# PIC_PROTO-BOARD-SMD.net
KiCad netlist of a schematic drawn in EAGLE
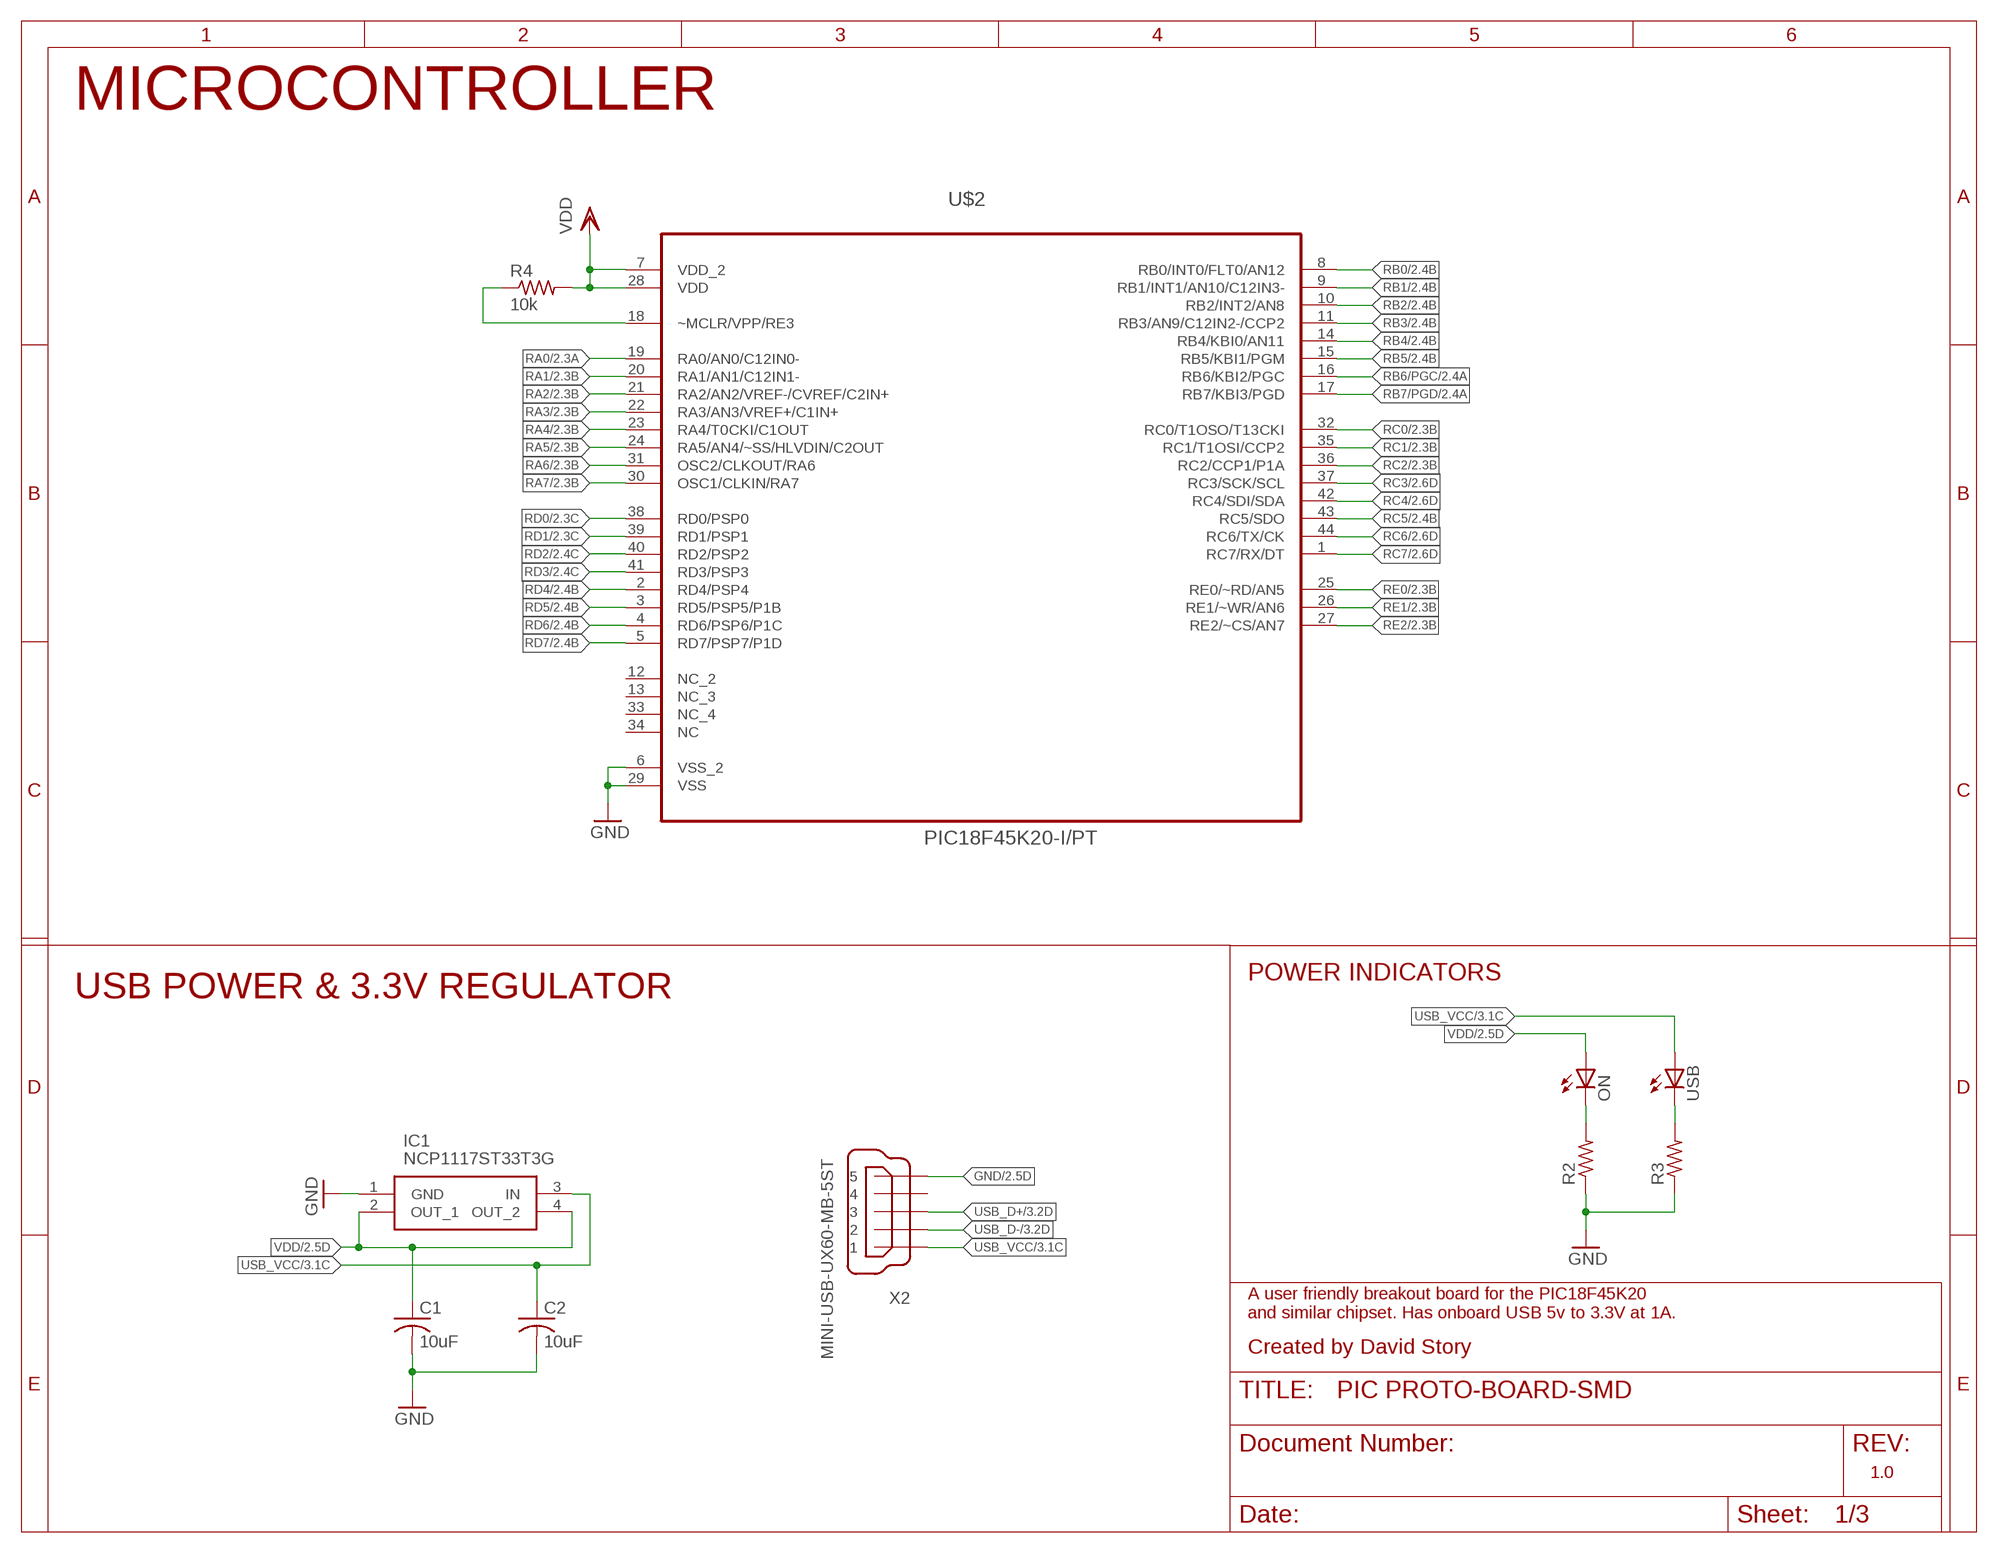
[diagram p0: schematic, sheet 1]
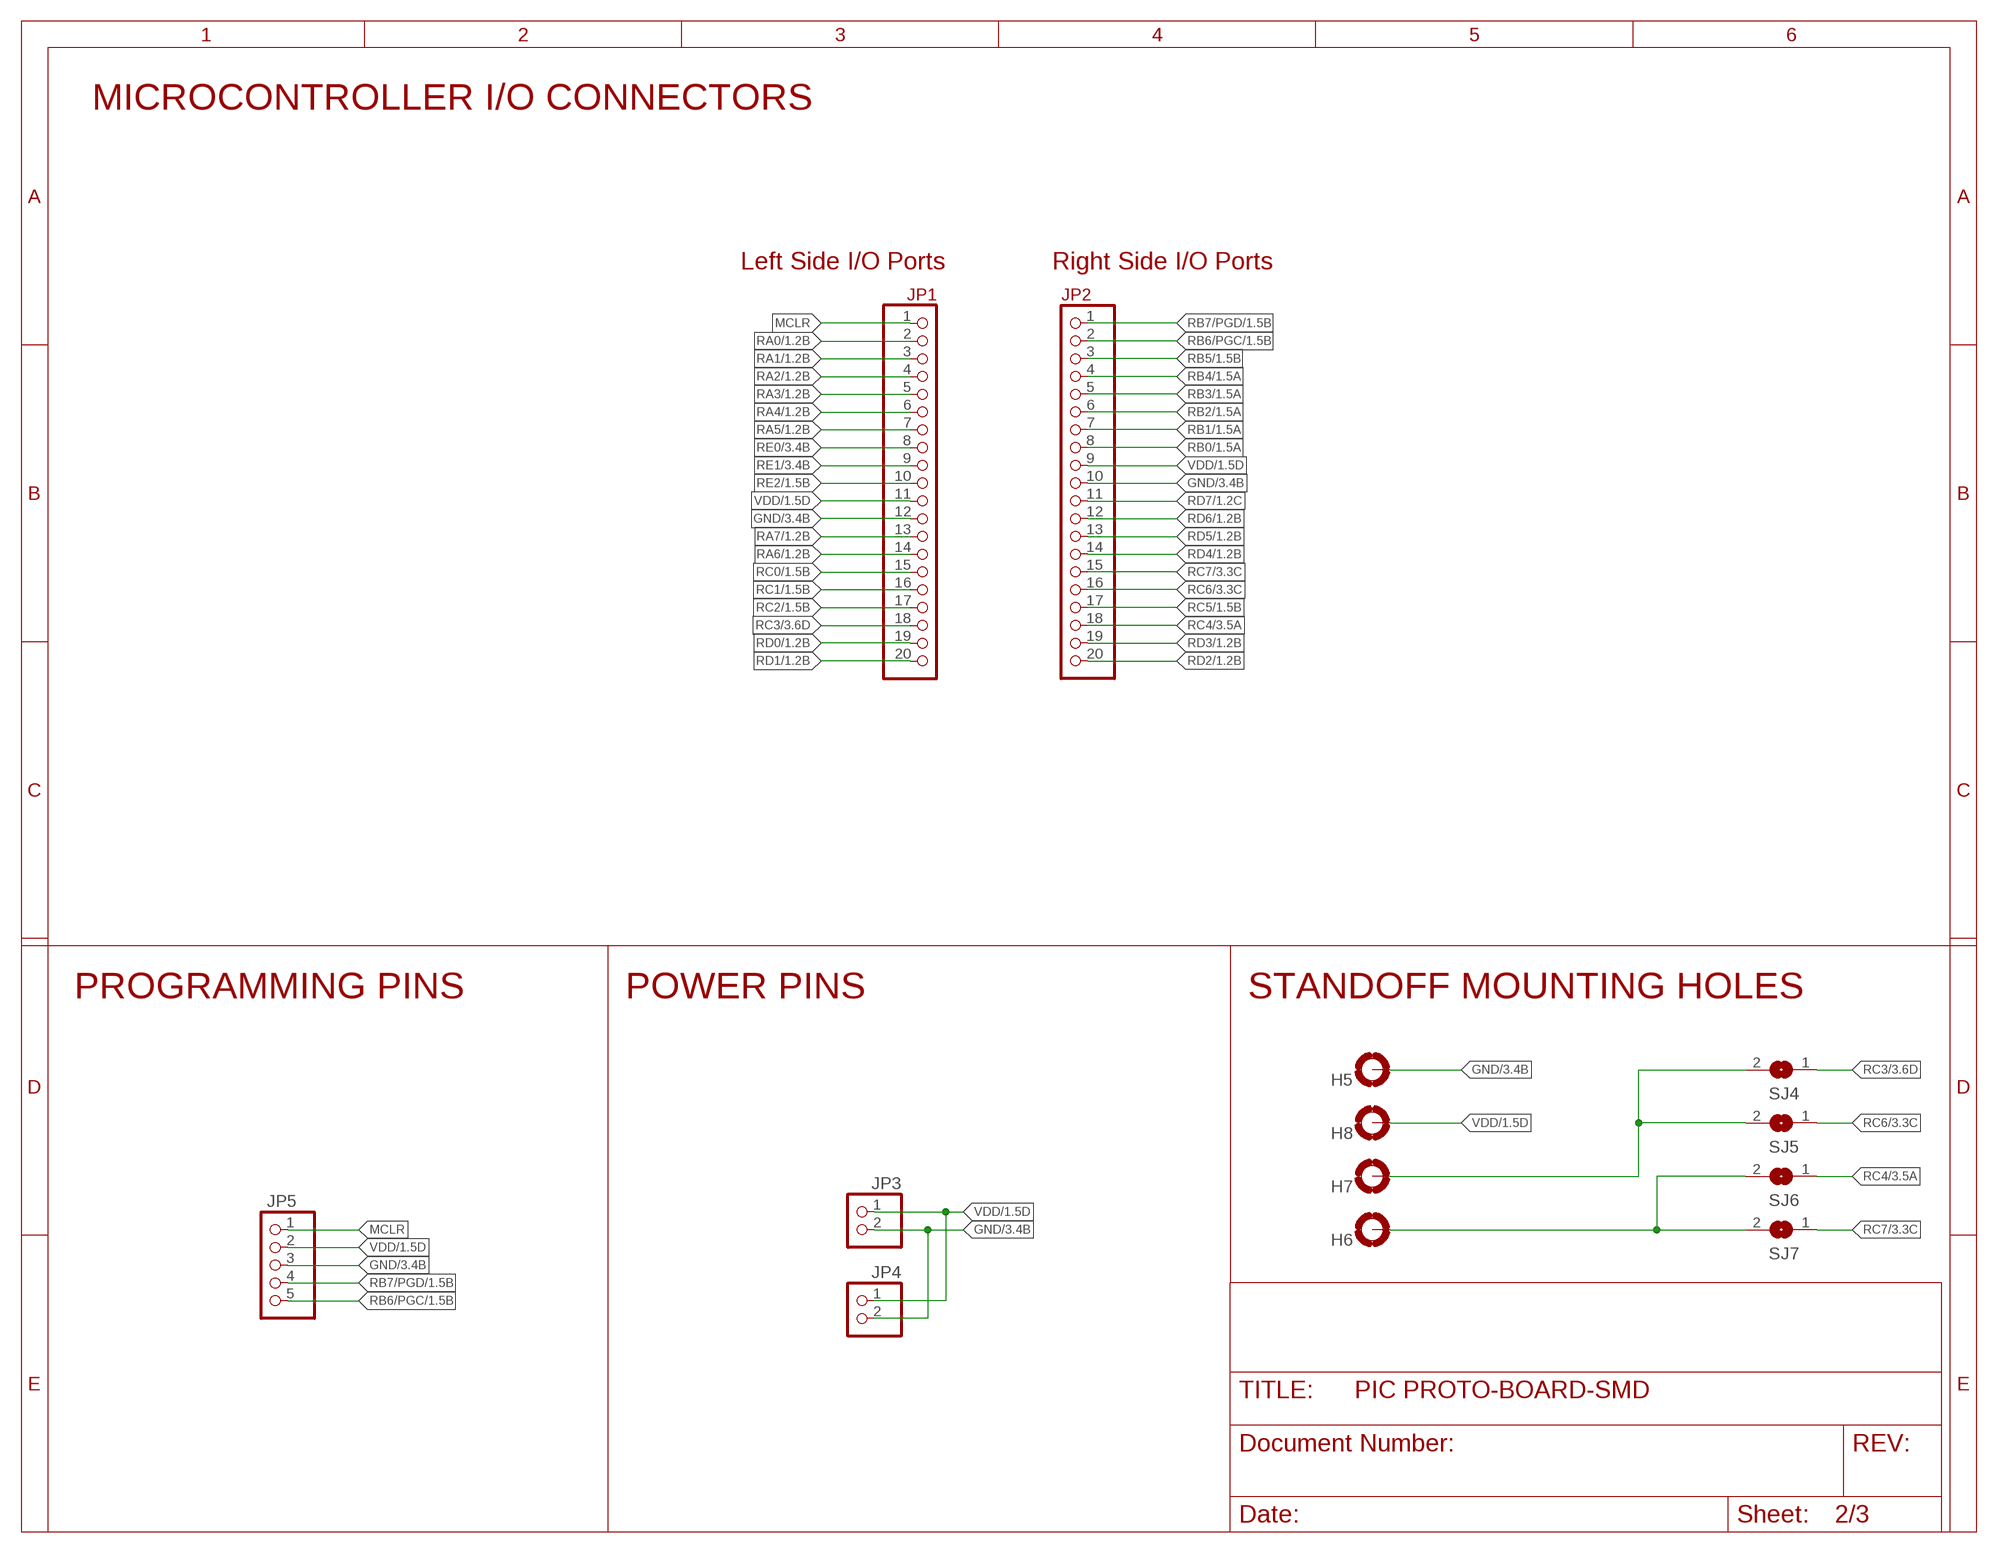
[diagram p1: schematic, sheet 2]
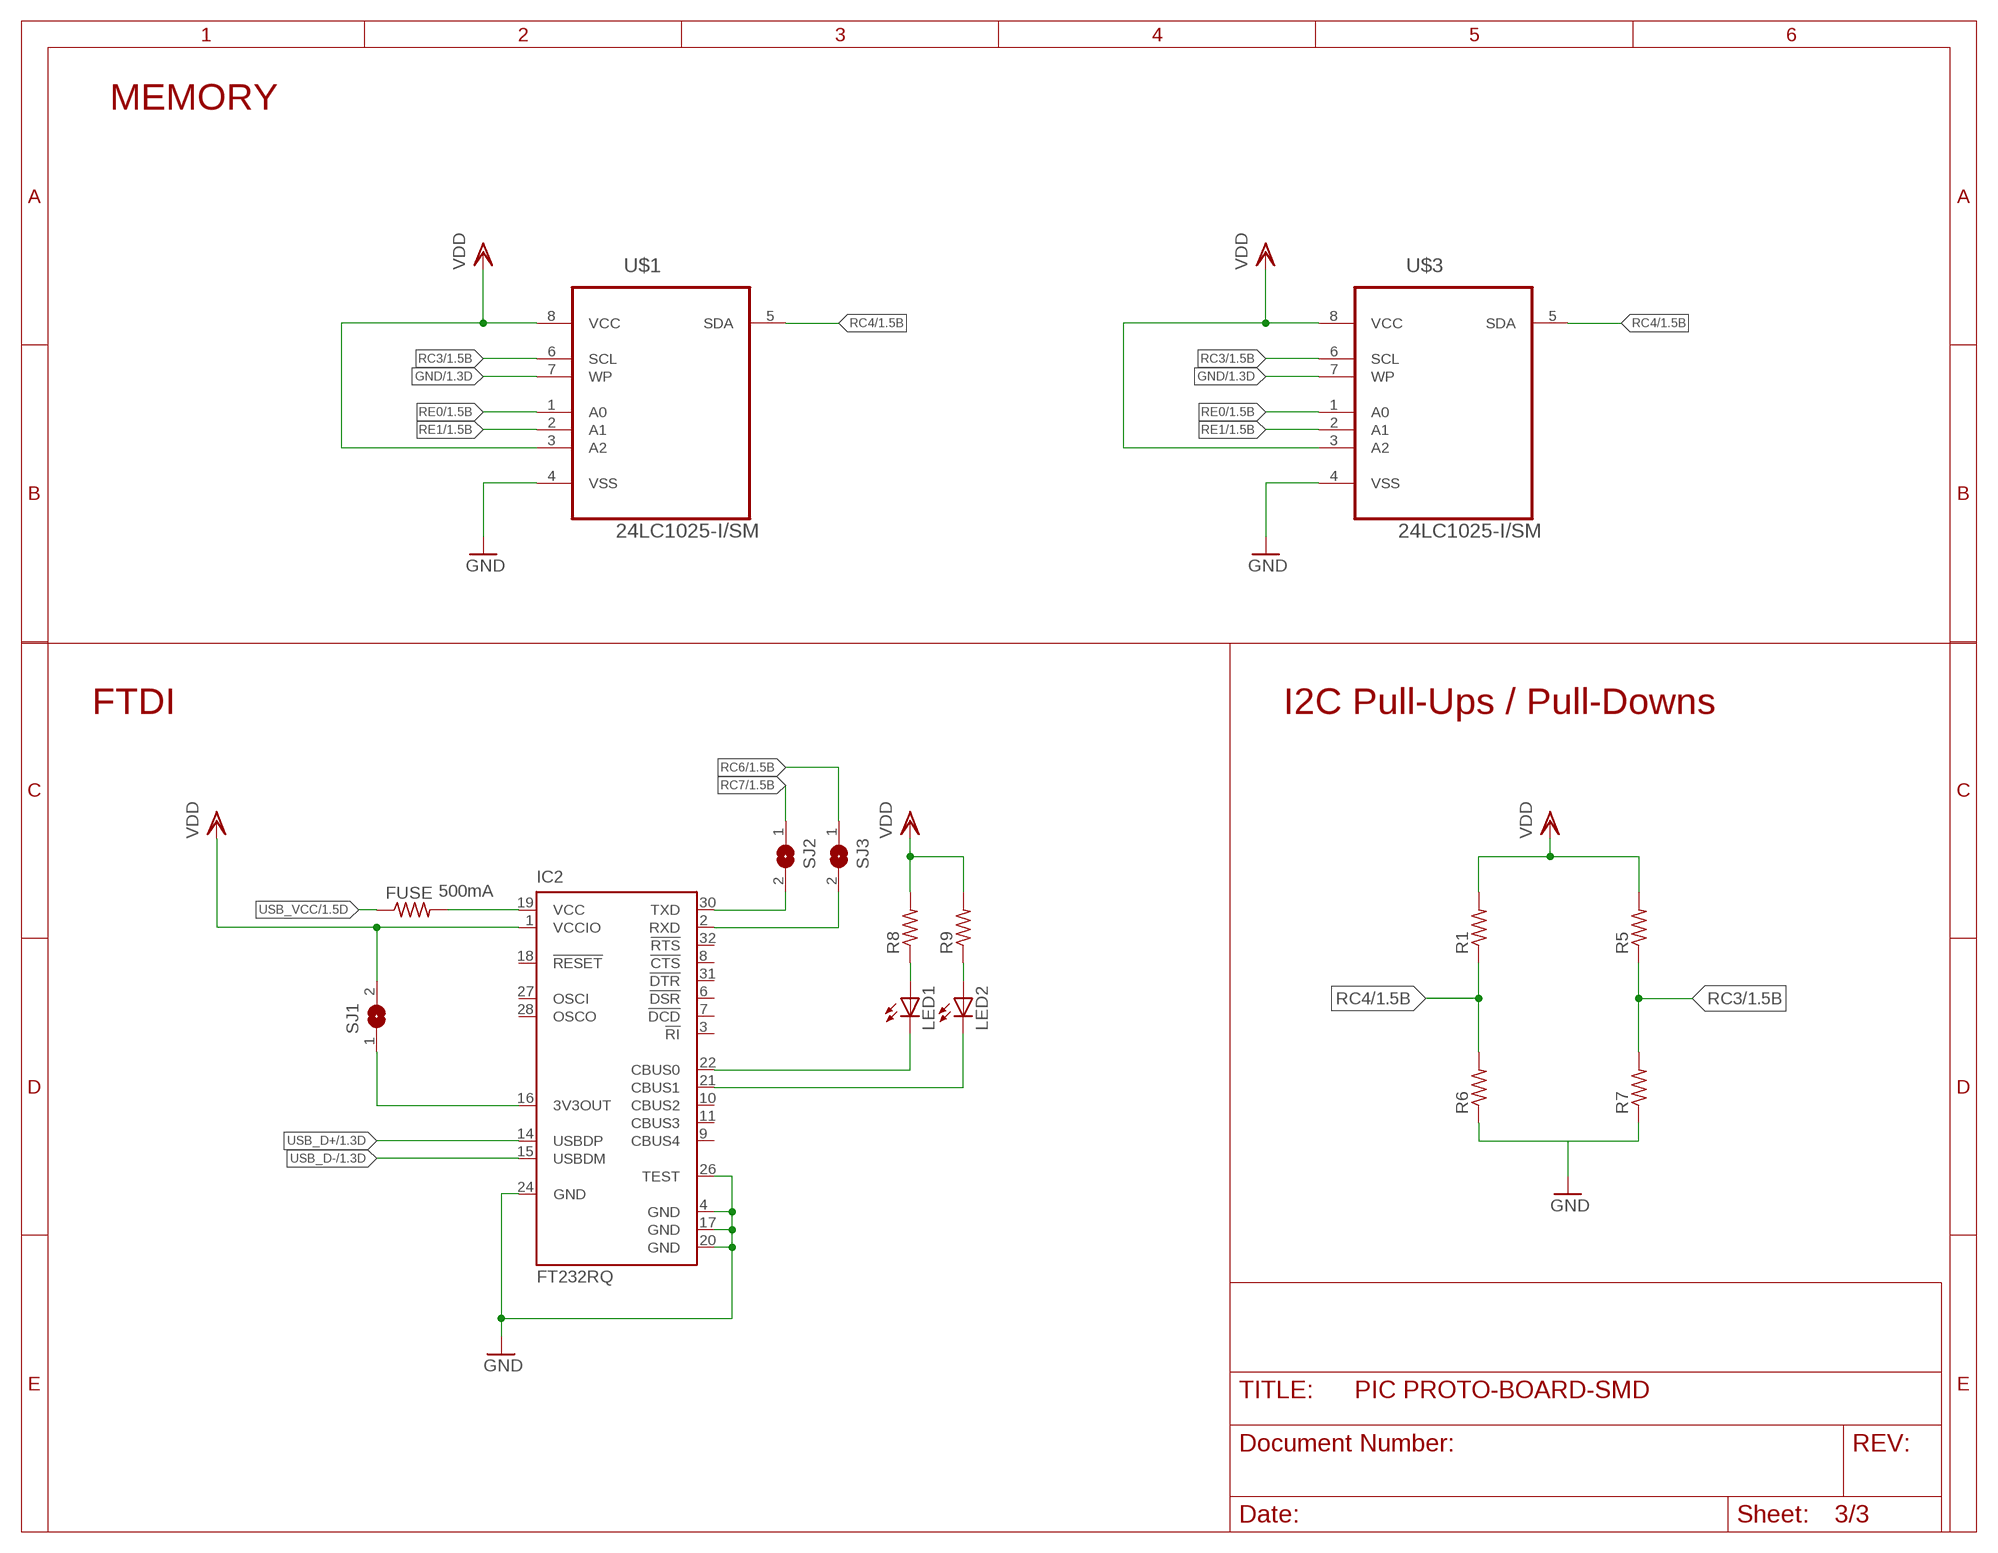
[diagram p2: schematic, sheet 3]

(export (version "E")
  (design (tool "Eeschema 10.0.6"))
  (components
    (comp (ref "C1")
      (value "10uF")
      (footprint "eagle-import:C0805")
      (libsource (lib "eagle-import") (part "C-USC0805"))
    )
    (comp (ref "C2")
      (value "10uF")
      (footprint "eagle-import:C0805")
      (libsource (lib "eagle-import") (part "C-USC0805"))
    )
    (comp (ref "IC1")
      (value "NCP1117ST33T3G")
      (footprint "eagle-import:SOT230P700X180-4N")
      (fields (field (name "MOUSER_PART_NUMBER") "863-NCP1117ST33T3G"))
      (libsource (lib "eagle-import") (part "NCP1117ST33T3G"))
    )
    (comp (ref "ON")
      (value "LEDCHIP-LED0603")
      (footprint "eagle-import:CHIP-LED0603")
      (libsource (lib "eagle-import") (part "LEDCHIP-LED0603"))
    )
    (comp (ref "R2")
      (value "R-US_R0603")
      (footprint "eagle-import:R0603")
      (libsource (lib "eagle-import") (part "R-US_R0603"))
    )
    (comp (ref "R3")
      (value "R-US_R0603")
      (footprint "eagle-import:R0603")
      (libsource (lib "eagle-import") (part "R-US_R0603"))
    )
    (comp (ref "R4")
      (value "10k")
      (footprint "eagle-import:R0805")
      (libsource (lib "eagle-import") (part "R-US_R0805"))
    )
    (comp (ref "U$2")
      (value "PIC18F45K20-I/PT")
      (footprint "eagle-import:QFP80P1200X1200X120-44N")
      (libsource (lib "eagle-import") (part "PIC18F45K20-I/PT"))
    )
    (comp (ref "USB")
      (value "LEDCHIP-LED0603")
      (footprint "eagle-import:CHIP-LED0603")
      (libsource (lib "eagle-import") (part "LEDCHIP-LED0603"))
    )
    (comp (ref "X2")
      (value "MINI-USB-UX60-MB-5ST")
      (footprint "eagle-import:UX60-MB-5ST")
      (libsource (lib "eagle-import") (part "MINI-USB-UX60-MB-5ST"))
    )
    (comp (ref "H5")
      (value "MOUNT-PAD-ROUND3.3")
      (footprint "eagle-import:3,3-PAD")
      (libsource (lib "eagle-import") (part "MOUNT-PAD-ROUND3.3"))
    )
    (comp (ref "H6")
      (value "MOUNT-PAD-ROUND3.3")
      (footprint "eagle-import:3,3-PAD")
      (libsource (lib "eagle-import") (part "MOUNT-PAD-ROUND3.3"))
    )
    (comp (ref "H7")
      (value "MOUNT-PAD-ROUND3.3")
      (footprint "eagle-import:3,3-PAD")
      (libsource (lib "eagle-import") (part "MOUNT-PAD-ROUND3.3"))
    )
    (comp (ref "H8")
      (value "MOUNT-PAD-ROUND3.3")
      (footprint "eagle-import:3,3-PAD")
      (libsource (lib "eagle-import") (part "MOUNT-PAD-ROUND3.3"))
    )
    (comp (ref "JP1")
      (value "PINHD-1X20")
      (footprint "eagle-import:1X20")
      (libsource (lib "eagle-import") (part "PINHD-1X20"))
    )
    (comp (ref "JP2")
      (value "PINHD-1X20")
      (footprint "eagle-import:1X20")
      (libsource (lib "eagle-import") (part "PINHD-1X20"))
    )
    (comp (ref "JP3")
      (value "PINHD-1X2")
      (footprint "eagle-import:1X02")
      (libsource (lib "eagle-import") (part "PINHD-1X2"))
    )
    (comp (ref "JP4")
      (value "PINHD-1X2")
      (footprint "eagle-import:1X02")
      (libsource (lib "eagle-import") (part "PINHD-1X2"))
    )
    (comp (ref "JP5")
      (value "PINHD-1X5")
      (footprint "eagle-import:1X05")
      (libsource (lib "eagle-import") (part "PINHD-1X5"))
    )
    (comp (ref "SJ4") (value "SJ") (footprint "eagle-import:SJ") (libsource (lib "eagle-import") (part "SJ")))
    (comp (ref "SJ5") (value "SJ") (footprint "eagle-import:SJ") (libsource (lib "eagle-import") (part "SJ")))
    (comp (ref "SJ6") (value "SJ") (footprint "eagle-import:SJ") (libsource (lib "eagle-import") (part "SJ")))
    (comp (ref "SJ7") (value "SJ") (footprint "eagle-import:SJ") (libsource (lib "eagle-import") (part "SJ")))
    (comp (ref "FUSE")
      (value "500mA")
      (footprint "eagle-import:M0805")
      (libsource (lib "eagle-import") (part "R-US_M0805"))
    )
    (comp (ref "IC2")
      (value "FT232RQ")
      (footprint "eagle-import:QFN32")
      (libsource (lib "eagle-import") (part "FT232RQ"))
    )
    (comp (ref "LED1")
      (value "LEDSML0603")
      (footprint "eagle-import:SML0603")
      (libsource (lib "eagle-import") (part "LEDSML0603"))
    )
    (comp (ref "LED2")
      (value "LEDSML0603")
      (footprint "eagle-import:SML0603")
      (libsource (lib "eagle-import") (part "LEDSML0603"))
    )
    (comp (ref "R1")
      (value "R-US_R0805")
      (footprint "eagle-import:R0805")
      (libsource (lib "eagle-import") (part "R-US_R0805"))
    )
    (comp (ref "R5")
      (value "R-US_R0805")
      (footprint "eagle-import:R0805")
      (libsource (lib "eagle-import") (part "R-US_R0805"))
    )
    (comp (ref "R6")
      (value "R-US_R0805")
      (footprint "eagle-import:R0805")
      (libsource (lib "eagle-import") (part "R-US_R0805"))
    )
    (comp (ref "R7")
      (value "R-US_R0805")
      (footprint "eagle-import:R0805")
      (libsource (lib "eagle-import") (part "R-US_R0805"))
    )
    (comp (ref "R8")
      (value "R-US_R0805")
      (footprint "eagle-import:R0805")
      (libsource (lib "eagle-import") (part "R-US_R0805"))
    )
    (comp (ref "R9")
      (value "R-US_R0805")
      (footprint "eagle-import:R0805")
      (libsource (lib "eagle-import") (part "R-US_R0805"))
    )
    (comp (ref "SJ1") (value "SJ") (footprint "eagle-import:SJ") (libsource (lib "eagle-import") (part "SJ")))
    (comp (ref "SJ2") (value "SJ") (footprint "eagle-import:SJ") (libsource (lib "eagle-import") (part "SJ")))
    (comp (ref "SJ3") (value "SJ") (footprint "eagle-import:SJ") (libsource (lib "eagle-import") (part "SJ")))
    (comp (ref "U$1")
      (value "24LC1025-I/SM")
      (footprint "eagle-import:SOIC127P794X203-8N")
      (libsource (lib "eagle-import") (part "24LC1025-I/SM"))
    )
    (comp (ref "U$3")
      (value "24LC1025-I/SM")
      (footprint "eagle-import:SOIC127P794X203-8N")
      (libsource (lib "eagle-import") (part "24LC1025-I/SM"))
    )
  )
  (nets
    (net (code "1") (name "GND") (class "Default")
      (node (ref "C1") (pin "2") (pinfunction "2_2") (pintype "passive"))
      (node (ref "C2") (pin "2") (pinfunction "2_2") (pintype "passive"))
      (node (ref "H5") (pin "B3,3") (pinfunction "MOUNT_B3,3") (pintype "passive"))
      (node (ref "IC1") (pin "1") (pinfunction "GND_1") (pintype "power_in"))
      (node (ref "IC2") (pin "17") (pinfunction "GND_17") (pintype "power_in"))
      (node (ref "IC2") (pin "20") (pinfunction "GND_20") (pintype "power_in"))
      (node (ref "IC2") (pin "24") (pinfunction "GND_24") (pintype "power_in"))
      (node (ref "IC2") (pin "26") (pinfunction "TEST_26") (pintype "input"))
      (node (ref "IC2") (pin "4") (pinfunction "GND_4") (pintype "power_in"))
      (node (ref "JP1") (pin "12") (pinfunction "12_12") (pintype "passive"))
      (node (ref "JP2") (pin "10") (pinfunction "10_10") (pintype "passive"))
      (node (ref "JP3") (pin "2") (pinfunction "2_2") (pintype "passive"))
      (node (ref "JP4") (pin "2") (pinfunction "2_2") (pintype "passive"))
      (node (ref "JP5") (pin "3") (pinfunction "3_3") (pintype "passive"))
      (node (ref "R2") (pin "1") (pinfunction "1_1") (pintype "passive"))
      (node (ref "R3") (pin "1") (pinfunction "1_1") (pintype "passive"))
      (node (ref "R6") (pin "1") (pinfunction "1_1") (pintype "passive"))
      (node (ref "R7") (pin "1") (pinfunction "1_1") (pintype "passive"))
      (node (ref "U$1") (pin "4") (pinfunction "VSS_4") (pintype "passive"))
      (node (ref "U$1") (pin "7") (pinfunction "WP_7") (pintype "input"))
      (node (ref "U$2") (pin "29") (pinfunction "VSS_29") (pintype "power_in"))
      (node (ref "U$2") (pin "6") (pinfunction "VSS_2_6") (pintype "power_in"))
      (node (ref "U$3") (pin "4") (pinfunction "VSS_4") (pintype "passive"))
      (node (ref "U$3") (pin "7") (pinfunction "WP_7") (pintype "input"))
      (node (ref "X2") (pin "5") (pinfunction "5_5") (pintype "input"))
    )
    (net (code "2") (name "MCLR") (class "Default")
      (node (ref "JP1") (pin "1") (pinfunction "1_1") (pintype "passive"))
      (node (ref "JP5") (pin "1") (pinfunction "1_1") (pintype "passive"))
      (node (ref "R4") (pin "1") (pinfunction "1_1") (pintype "passive"))
      (node (ref "U$2") (pin "18") (pinfunction "~{MCLR/VPP/RE3}_18") (pintype "input"))
    )
    (net (code "3") (name "Net-(H6-MOUNT)") (class "Default")
      (node (ref "H6") (pin "B3,3") (pinfunction "MOUNT_B3,3") (pintype "passive"))
      (node (ref "SJ6") (pin "2") (pinfunction "2_2") (pintype "passive"))
      (node (ref "SJ7") (pin "2") (pinfunction "2_2") (pintype "passive"))
    )
    (net (code "4") (name "Net-(H7-MOUNT)") (class "Default")
      (node (ref "H7") (pin "B3,3") (pinfunction "MOUNT_B3,3") (pintype "passive"))
      (node (ref "SJ4") (pin "2") (pinfunction "2_2") (pintype "passive"))
      (node (ref "SJ5") (pin "2") (pinfunction "2_2") (pintype "passive"))
    )
    (net (code "5") (name "Net-(IC2-3V3OUT)") (class "Default")
      (node (ref "IC2") (pin "16") (pinfunction "3V3OUT_16") (pintype "output"))
      (node (ref "SJ1") (pin "1") (pinfunction "1_1") (pintype "passive"))
    )
    (net (code "6") (name "Net-(IC2-CBUS0)") (class "Default")
      (node (ref "IC2") (pin "22") (pinfunction "CBUS0_22") (pintype "bidirectional"))
      (node (ref "LED1") (pin "C") (pinfunction "C_C") (pintype "passive"))
    )
    (net (code "7") (name "Net-(IC2-CBUS1)") (class "Default")
      (node (ref "IC2") (pin "21") (pinfunction "CBUS1_21") (pintype "bidirectional"))
      (node (ref "LED2") (pin "C") (pinfunction "C_C") (pintype "passive"))
    )
    (net (code "8") (name "Net-(IC2-RXD)") (class "Default")
      (node (ref "IC2") (pin "2") (pinfunction "RXD_2") (pintype "input"))
      (node (ref "SJ3") (pin "2") (pinfunction "2_2") (pintype "passive"))
    )
    (net (code "9") (name "Net-(IC2-TXD)") (class "Default")
      (node (ref "IC2") (pin "30") (pinfunction "TXD_30") (pintype "output"))
      (node (ref "SJ2") (pin "2") (pinfunction "2_2") (pintype "passive"))
    )
    (net (code "10") (name "Net-(IC2-VCC)") (class "Default")
      (node (ref "FUSE") (pin "2") (pinfunction "2_2") (pintype "passive"))
      (node (ref "IC2") (pin "19") (pinfunction "VCC_19") (pintype "power_in"))
    )
    (net (code "11") (name "Net-(LED1-PadA)") (class "Default")
      (node (ref "LED1") (pin "A") (pinfunction "A_A") (pintype "passive"))
      (node (ref "R8") (pin "1") (pinfunction "1_1") (pintype "passive"))
    )
    (net (code "12") (name "Net-(LED2-PadA)") (class "Default")
      (node (ref "LED2") (pin "A") (pinfunction "A_A") (pintype "passive"))
      (node (ref "R9") (pin "1") (pinfunction "1_1") (pintype "passive"))
    )
    (net (code "13") (name "Net-(ON-PadC)") (class "Default")
      (node (ref "ON") (pin "C") (pinfunction "C_C") (pintype "passive"))
      (node (ref "R2") (pin "2") (pinfunction "2_2") (pintype "passive"))
    )
    (net (code "14") (name "Net-(R3-Pad2)") (class "Default")
      (node (ref "R3") (pin "2") (pinfunction "2_2") (pintype "passive"))
      (node (ref "USB") (pin "C") (pinfunction "C_C") (pintype "passive"))
    )
    (net (code "15") (name "RA0") (class "Default")
      (node (ref "JP1") (pin "2") (pinfunction "2_2") (pintype "passive"))
      (node (ref "U$2") (pin "19") (pinfunction "RA0/AN0/C12IN0-_19") (pintype "bidirectional"))
    )
    (net (code "16") (name "RA1") (class "Default")
      (node (ref "JP1") (pin "3") (pinfunction "3_3") (pintype "passive"))
      (node (ref "U$2") (pin "20") (pinfunction "RA1/AN1/C12IN1-_20") (pintype "bidirectional"))
    )
    (net (code "17") (name "RA2") (class "Default")
      (node (ref "JP1") (pin "4") (pinfunction "4_4") (pintype "passive"))
      (node (ref "U$2") (pin "21") (pinfunction "RA2/AN2/VREF-/CVREF/C2IN+_21") (pintype "bidirectional"))
    )
    (net (code "18") (name "RA3") (class "Default")
      (node (ref "JP1") (pin "5") (pinfunction "5_5") (pintype "passive"))
      (node (ref "U$2") (pin "22") (pinfunction "RA3/AN3/VREF+/C1IN+_22") (pintype "bidirectional"))
    )
    (net (code "19") (name "RA4") (class "Default")
      (node (ref "JP1") (pin "6") (pinfunction "6_6") (pintype "passive"))
      (node (ref "U$2") (pin "23") (pinfunction "RA4/T0CKI/C1OUT_23") (pintype "bidirectional"))
    )
    (net (code "20") (name "RA5") (class "Default")
      (node (ref "JP1") (pin "7") (pinfunction "7_7") (pintype "passive"))
      (node (ref "U$2") (pin "24") (pinfunction "RA5/AN4/~{SS/HLVDIN/C2OUT}_24") (pintype "bidirectional"))
    )
    (net (code "21") (name "RA6") (class "Default")
      (node (ref "JP1") (pin "14") (pinfunction "14_14") (pintype "passive"))
      (node (ref "U$2") (pin "31") (pinfunction "OSC2/CLKOUT/RA6_31") (pintype "bidirectional"))
    )
    (net (code "22") (name "RA7") (class "Default")
      (node (ref "JP1") (pin "13") (pinfunction "13_13") (pintype "passive"))
      (node (ref "U$2") (pin "30") (pinfunction "OSC1/CLKIN/RA7_30") (pintype "bidirectional"))
    )
    (net (code "23") (name "RB0") (class "Default")
      (node (ref "JP2") (pin "8") (pinfunction "8_8") (pintype "passive"))
      (node (ref "U$2") (pin "8") (pinfunction "RB0/INT0/FLT0/AN12_8") (pintype "bidirectional"))
    )
    (net (code "24") (name "RB1") (class "Default")
      (node (ref "JP2") (pin "7") (pinfunction "7_7") (pintype "passive"))
      (node (ref "U$2") (pin "9") (pinfunction "RB1/INT1/AN10/C12IN3-_9") (pintype "bidirectional"))
    )
    (net (code "25") (name "RB2") (class "Default")
      (node (ref "JP2") (pin "6") (pinfunction "6_6") (pintype "passive"))
      (node (ref "U$2") (pin "10") (pinfunction "RB2/INT2/AN8_10") (pintype "bidirectional"))
    )
    (net (code "26") (name "RB3") (class "Default")
      (node (ref "JP2") (pin "5") (pinfunction "5_5") (pintype "passive"))
      (node (ref "U$2") (pin "11") (pinfunction "RB3/AN9/C12IN2-/CCP2_11") (pintype "bidirectional"))
    )
    (net (code "27") (name "RB4") (class "Default")
      (node (ref "JP2") (pin "4") (pinfunction "4_4") (pintype "passive"))
      (node (ref "U$2") (pin "14") (pinfunction "RB4/KBI0/AN11_14") (pintype "bidirectional"))
    )
    (net (code "28") (name "RB5") (class "Default")
      (node (ref "JP2") (pin "3") (pinfunction "3_3") (pintype "passive"))
      (node (ref "U$2") (pin "15") (pinfunction "RB5/KBI1/PGM_15") (pintype "bidirectional"))
    )
    (net (code "29") (name "RB6{slash}PGC") (class "Default")
      (node (ref "JP2") (pin "2") (pinfunction "2_2") (pintype "passive"))
      (node (ref "JP5") (pin "5") (pinfunction "5_5") (pintype "passive"))
      (node (ref "U$2") (pin "16") (pinfunction "RB6/KBI2/PGC_16") (pintype "bidirectional"))
    )
    (net (code "30") (name "RB7{slash}PGD") (class "Default")
      (node (ref "JP2") (pin "1") (pinfunction "1_1") (pintype "passive"))
      (node (ref "JP5") (pin "4") (pinfunction "4_4") (pintype "passive"))
      (node (ref "U$2") (pin "17") (pinfunction "RB7/KBI3/PGD_17") (pintype "bidirectional"))
    )
    (net (code "31") (name "RC0") (class "Default")
      (node (ref "JP1") (pin "15") (pinfunction "15_15") (pintype "passive"))
      (node (ref "U$2") (pin "32") (pinfunction "RC0/T1OSO/T13CKI_32") (pintype "bidirectional"))
    )
    (net (code "32") (name "RC1") (class "Default")
      (node (ref "JP1") (pin "16") (pinfunction "16_16") (pintype "passive"))
      (node (ref "U$2") (pin "35") (pinfunction "RC1/T1OSI/CCP2_35") (pintype "bidirectional"))
    )
    (net (code "33") (name "RC2") (class "Default")
      (node (ref "JP1") (pin "17") (pinfunction "17_17") (pintype "passive"))
      (node (ref "U$2") (pin "36") (pinfunction "RC2/CCP1/P1A_36") (pintype "bidirectional"))
    )
    (net (code "34") (name "RC3") (class "Default")
      (node (ref "JP1") (pin "18") (pinfunction "18_18") (pintype "passive"))
      (node (ref "R5") (pin "1") (pinfunction "1_1") (pintype "passive"))
      (node (ref "R7") (pin "2") (pinfunction "2_2") (pintype "passive"))
      (node (ref "SJ4") (pin "1") (pinfunction "1_1") (pintype "passive"))
      (node (ref "U$1") (pin "6") (pinfunction "SCL_6") (pintype "input"))
      (node (ref "U$2") (pin "37") (pinfunction "RC3/SCK/SCL_37") (pintype "bidirectional"))
      (node (ref "U$3") (pin "6") (pinfunction "SCL_6") (pintype "input"))
    )
    (net (code "35") (name "RC4") (class "Default")
      (node (ref "JP2") (pin "18") (pinfunction "18_18") (pintype "passive"))
      (node (ref "R1") (pin "1") (pinfunction "1_1") (pintype "passive"))
      (node (ref "R6") (pin "2") (pinfunction "2_2") (pintype "passive"))
      (node (ref "SJ6") (pin "1") (pinfunction "1_1") (pintype "passive"))
      (node (ref "U$1") (pin "5") (pinfunction "SDA_5") (pintype "bidirectional"))
      (node (ref "U$2") (pin "42") (pinfunction "RC4/SDI/SDA_42") (pintype "bidirectional"))
      (node (ref "U$3") (pin "5") (pinfunction "SDA_5") (pintype "bidirectional"))
    )
    (net (code "36") (name "RC5") (class "Default")
      (node (ref "JP2") (pin "17") (pinfunction "17_17") (pintype "passive"))
      (node (ref "U$2") (pin "43") (pinfunction "RC5/SDO_43") (pintype "bidirectional"))
    )
    (net (code "37") (name "RC6") (class "Default")
      (node (ref "JP2") (pin "16") (pinfunction "16_16") (pintype "passive"))
      (node (ref "SJ3") (pin "1") (pinfunction "1_1") (pintype "passive"))
      (node (ref "SJ5") (pin "1") (pinfunction "1_1") (pintype "passive"))
      (node (ref "U$2") (pin "44") (pinfunction "RC6/TX/CK_44") (pintype "bidirectional"))
    )
    (net (code "38") (name "RC7") (class "Default")
      (node (ref "JP2") (pin "15") (pinfunction "15_15") (pintype "passive"))
      (node (ref "SJ2") (pin "1") (pinfunction "1_1") (pintype "passive"))
      (node (ref "SJ7") (pin "1") (pinfunction "1_1") (pintype "passive"))
      (node (ref "U$2") (pin "1") (pinfunction "RC7/RX/DT_1") (pintype "bidirectional"))
    )
    (net (code "39") (name "RD0") (class "Default")
      (node (ref "JP1") (pin "19") (pinfunction "19_19") (pintype "passive"))
      (node (ref "U$2") (pin "38") (pinfunction "RD0/PSP0_38") (pintype "bidirectional"))
    )
    (net (code "40") (name "RD1") (class "Default")
      (node (ref "JP1") (pin "20") (pinfunction "20_20") (pintype "passive"))
      (node (ref "U$2") (pin "39") (pinfunction "RD1/PSP1_39") (pintype "bidirectional"))
    )
    (net (code "41") (name "RD2") (class "Default")
      (node (ref "JP2") (pin "20") (pinfunction "20_20") (pintype "passive"))
      (node (ref "U$2") (pin "40") (pinfunction "RD2/PSP2_40") (pintype "bidirectional"))
    )
    (net (code "42") (name "RD3") (class "Default")
      (node (ref "JP2") (pin "19") (pinfunction "19_19") (pintype "passive"))
      (node (ref "U$2") (pin "41") (pinfunction "RD3/PSP3_41") (pintype "bidirectional"))
    )
    (net (code "43") (name "RD4") (class "Default")
      (node (ref "JP2") (pin "14") (pinfunction "14_14") (pintype "passive"))
      (node (ref "U$2") (pin "2") (pinfunction "RD4/PSP4_2") (pintype "bidirectional"))
    )
    (net (code "44") (name "RD5") (class "Default")
      (node (ref "JP2") (pin "13") (pinfunction "13_13") (pintype "passive"))
      (node (ref "U$2") (pin "3") (pinfunction "RD5/PSP5/P1B_3") (pintype "bidirectional"))
    )
    (net (code "45") (name "RD6") (class "Default")
      (node (ref "JP2") (pin "12") (pinfunction "12_12") (pintype "passive"))
      (node (ref "U$2") (pin "4") (pinfunction "RD6/PSP6/P1C_4") (pintype "bidirectional"))
    )
    (net (code "46") (name "RD7") (class "Default")
      (node (ref "JP2") (pin "11") (pinfunction "11_11") (pintype "passive"))
      (node (ref "U$2") (pin "5") (pinfunction "RD7/PSP7/P1D_5") (pintype "bidirectional"))
    )
    (net (code "47") (name "RE0") (class "Default")
      (node (ref "JP1") (pin "8") (pinfunction "8_8") (pintype "passive"))
      (node (ref "U$1") (pin "1") (pinfunction "A0_1") (pintype "input"))
      (node (ref "U$2") (pin "25") (pinfunction "RE0/~{RD/AN5}_25") (pintype "bidirectional"))
      (node (ref "U$3") (pin "1") (pinfunction "A0_1") (pintype "input"))
    )
    (net (code "48") (name "RE1") (class "Default")
      (node (ref "JP1") (pin "9") (pinfunction "9_9") (pintype "passive"))
      (node (ref "U$1") (pin "2") (pinfunction "A1_2") (pintype "input"))
      (node (ref "U$2") (pin "26") (pinfunction "RE1/~{WR/AN6}_26") (pintype "bidirectional"))
      (node (ref "U$3") (pin "2") (pinfunction "A1_2") (pintype "input"))
    )
    (net (code "49") (name "RE2") (class "Default")
      (node (ref "JP1") (pin "10") (pinfunction "10_10") (pintype "passive"))
      (node (ref "U$2") (pin "27") (pinfunction "RE2/~{CS/AN7}_27") (pintype "bidirectional"))
    )
    (net (code "50") (name "USB_D+") (class "Default")
      (node (ref "IC2") (pin "14") (pinfunction "USBDP_14") (pintype "bidirectional"))
      (node (ref "X2") (pin "3") (pinfunction "3_3") (pintype "input"))
    )
    (net (code "51") (name "USB_D-") (class "Default")
      (node (ref "IC2") (pin "15") (pinfunction "USBDM_15") (pintype "bidirectional"))
      (node (ref "X2") (pin "2") (pinfunction "2_2") (pintype "input"))
    )
    (net (code "52") (name "USB_VCC") (class "Default")
      (node (ref "C2") (pin "1") (pinfunction "1_1") (pintype "passive"))
      (node (ref "FUSE") (pin "1") (pinfunction "1_1") (pintype "passive"))
      (node (ref "IC1") (pin "3") (pinfunction "IN_3") (pintype "input"))
      (node (ref "USB") (pin "A") (pinfunction "A_A") (pintype "passive"))
      (node (ref "X2") (pin "1") (pinfunction "1_1") (pintype "input"))
    )
    (net (code "53") (name "VDD") (class "Default")
      (node (ref "C1") (pin "1") (pinfunction "1_1") (pintype "passive"))
      (node (ref "H8") (pin "B3,3") (pinfunction "MOUNT_B3,3") (pintype "passive"))
      (node (ref "IC1") (pin "2") (pinfunction "OUT_1_2") (pintype "output"))
      (node (ref "IC1") (pin "4") (pinfunction "OUT_2_4") (pintype "output"))
      (node (ref "IC2") (pin "1") (pinfunction "VCCIO_1") (pintype "power_in"))
      (node (ref "JP1") (pin "11") (pinfunction "11_11") (pintype "passive"))
      (node (ref "JP2") (pin "9") (pinfunction "9_9") (pintype "passive"))
      (node (ref "JP3") (pin "1") (pinfunction "1_1") (pintype "passive"))
      (node (ref "JP4") (pin "1") (pinfunction "1_1") (pintype "passive"))
      (node (ref "JP5") (pin "2") (pinfunction "2_2") (pintype "passive"))
      (node (ref "ON") (pin "A") (pinfunction "A_A") (pintype "passive"))
      (node (ref "R1") (pin "2") (pinfunction "2_2") (pintype "passive"))
      (node (ref "R4") (pin "2") (pinfunction "2_2") (pintype "passive"))
      (node (ref "R5") (pin "2") (pinfunction "2_2") (pintype "passive"))
      (node (ref "R8") (pin "2") (pinfunction "2_2") (pintype "passive"))
      (node (ref "R9") (pin "2") (pinfunction "2_2") (pintype "passive"))
      (node (ref "SJ1") (pin "2") (pinfunction "2_2") (pintype "passive"))
      (node (ref "U$1") (pin "3") (pinfunction "A2_3") (pintype "input"))
      (node (ref "U$1") (pin "8") (pinfunction "VCC_8") (pintype "power_in"))
      (node (ref "U$2") (pin "28") (pinfunction "VDD_28") (pintype "power_in"))
      (node (ref "U$2") (pin "7") (pinfunction "VDD_2_7") (pintype "power_in"))
      (node (ref "U$3") (pin "3") (pinfunction "A2_3") (pintype "input"))
      (node (ref "U$3") (pin "8") (pinfunction "VCC_8") (pintype "power_in"))
    )
    (net (code "54") (name "unconnected-(IC2-CBUS2-Pad10)") (class "Default")
      (node (ref "IC2") (pin "10") (pinfunction "CBUS2_10") (pintype "bidirectional"))
    )
    (net (code "55") (name "unconnected-(IC2-CBUS3-Pad11)") (class "Default")
      (node (ref "IC2") (pin "11") (pinfunction "CBUS3_11") (pintype "bidirectional"))
    )
    (net (code "56") (name "unconnected-(IC2-CBUS4-Pad9)") (class "Default")
      (node (ref "IC2") (pin "9") (pinfunction "CBUS4_9") (pintype "bidirectional"))
    )
    (net (code "57") (name "unconnected-(IC2-OSCI-Pad27)") (class "Default")
      (node (ref "IC2") (pin "27") (pinfunction "OSCI_27") (pintype "input"))
    )
    (net (code "58") (name "unconnected-(IC2-OSCO-Pad28)") (class "Default")
      (node (ref "IC2") (pin "28") (pinfunction "OSCO_28") (pintype "output"))
    )
    (net (code "59") (name "unconnected-(IC2-~{CTS}-Pad8)") (class "Default")
      (node (ref "IC2") (pin "8") (pinfunction "~{CTS}_8") (pintype "input"))
    )
    (net (code "60") (name "unconnected-(IC2-~{DCD}-Pad7)") (class "Default")
      (node (ref "IC2") (pin "7") (pinfunction "~{DCD}_7") (pintype "input"))
    )
    (net (code "61") (name "unconnected-(IC2-~{DSR}-Pad6)") (class "Default")
      (node (ref "IC2") (pin "6") (pinfunction "~{DSR}_6") (pintype "input"))
    )
    (net (code "62") (name "unconnected-(IC2-~{DTR}-Pad31)") (class "Default")
      (node (ref "IC2") (pin "31") (pinfunction "~{DTR}_31") (pintype "output"))
    )
    (net (code "63") (name "unconnected-(IC2-~{RESET}-Pad18)") (class "Default")
      (node (ref "IC2") (pin "18") (pinfunction "~{RESET}_18") (pintype "input"))
    )
    (net (code "64") (name "unconnected-(IC2-~{RI}-Pad3)") (class "Default")
      (node (ref "IC2") (pin "3") (pinfunction "~{RI}_3") (pintype "input"))
    )
    (net (code "65") (name "unconnected-(IC2-~{RTS}-Pad32)") (class "Default")
      (node (ref "IC2") (pin "32") (pinfunction "~{RTS}_32") (pintype "output"))
    )
    (net (code "66") (name "unconnected-(U$2-NC-Pad34)") (class "Default")
      (node (ref "U$2") (pin "34") (pinfunction "NC_34") (pintype "no_connect"))
    )
    (net (code "67") (name "unconnected-(U$2-NC_2-Pad12)") (class "Default")
      (node (ref "U$2") (pin "12") (pinfunction "NC_2_12") (pintype "no_connect"))
    )
    (net (code "68") (name "unconnected-(U$2-NC_3-Pad13)") (class "Default")
      (node (ref "U$2") (pin "13") (pinfunction "NC_3_13") (pintype "no_connect"))
    )
    (net (code "69") (name "unconnected-(U$2-NC_4-Pad33)") (class "Default")
      (node (ref "U$2") (pin "33") (pinfunction "NC_4_33") (pintype "no_connect"))
    )
    (net (code "70") (name "unconnected-(X2-Pad4)") (class "Default")
      (node (ref "X2") (pin "4") (pinfunction "4_4") (pintype "input"))
    )
  )
)
